# Power.net
KiCad netlist of a schematic drawn in Altium Designer
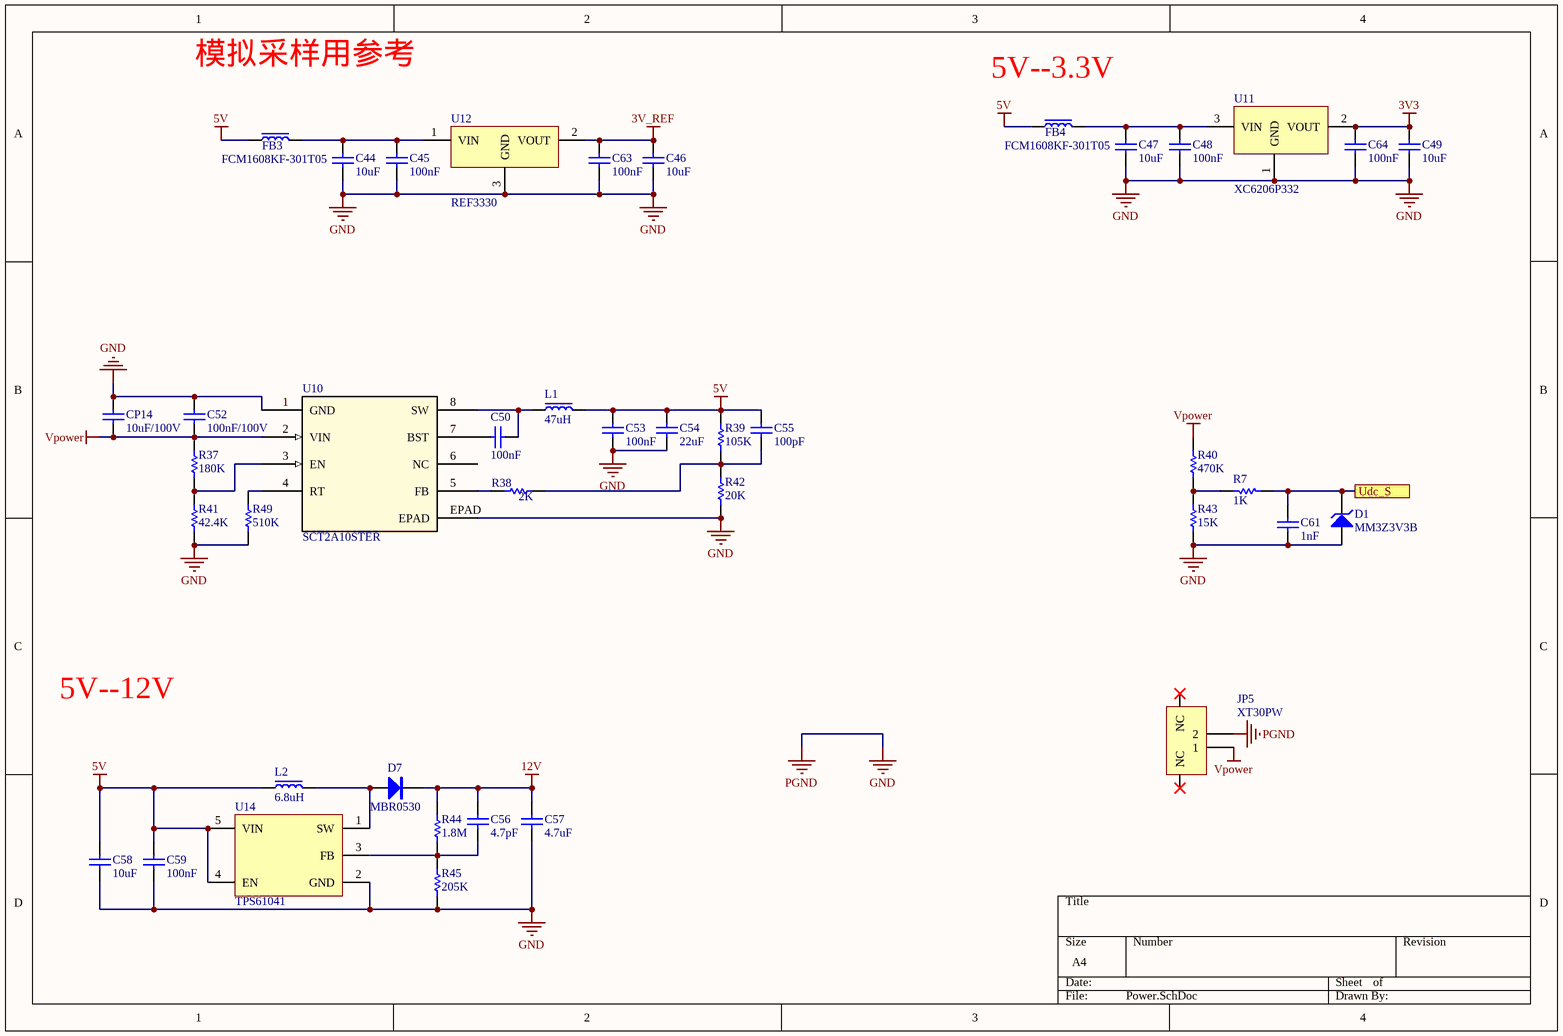
[diagram p0: Power.SchDoc]

(export (version "E")
  (design (tool "Eeschema 10.0.6"))
  (components
    (comp (ref "C44") (value "10uF") (footprint "C0603") (libsource (lib "Cap") (part "Cap")))
    (comp (ref "C45") (value "100nF") (footprint "C0603") (libsource (lib "Cap") (part "Cap")))
    (comp (ref "C46") (value "10uF") (footprint "C0603") (libsource (lib "Cap") (part "Cap")))
    (comp (ref "C47") (value "10uF") (footprint "C0603") (libsource (lib "Cap") (part "Cap")))
    (comp (ref "C48") (value "100nF") (footprint "C0603") (libsource (lib "Cap") (part "Cap")))
    (comp (ref "C49") (value "10uF") (footprint "C0603") (libsource (lib "Cap") (part "Cap")))
    (comp (ref "C50") (value "100nF") (footprint "C0603") (libsource (lib "Cap") (part "Cap")))
    (comp (ref "C52") (value "100nF/100V") (footprint "C0603") (libsource (lib "Cap") (part "Cap")))
    (comp (ref "C53") (value "100nF") (footprint "C0603") (libsource (lib "Cap") (part "Cap")))
    (comp (ref "C54") (value "22uF") (footprint "C0805") (libsource (lib "Cap") (part "Cap")))
    (comp (ref "C55") (value "100pF") (footprint "C0603") (libsource (lib "Cap") (part "Cap")))
    (comp (ref "C56") (value "4.7pF") (footprint "C0603") (libsource (lib "Cap") (part "Cap")))
    (comp (ref "C57") (value "4.7uF") (footprint "C0805") (libsource (lib "Cap") (part "Cap")))
    (comp (ref "C58") (value "10uF") (footprint "C0805") (libsource (lib "Cap") (part "Cap")))
    (comp (ref "C59") (value "100nF") (footprint "C0603") (libsource (lib "Cap") (part "Cap")))
    (comp (ref "C61") (value "1nF") (footprint "C0402") (libsource (lib "Cap") (part "Cap")))
    (comp (ref "C63") (value "100nF") (footprint "C0603") (libsource (lib "Cap") (part "Cap")))
    (comp (ref "C64") (value "100nF") (footprint "C0603") (libsource (lib "Cap") (part "Cap")))
    (comp (ref "CP14") (value "10uF/100V") (footprint "C1206") (libsource (lib "Cap") (part "Cap")))
    (comp (ref "D1")
      (value "MM3Z3V3B")
      (footprint "SOD-323")
      (description "3.14V~3.47V\r\n300mW")
      (libsource (lib "NTlib") (part "MM3Z3V3B"))
    )
    (comp (ref "D7")
      (value "MBR0530")
      (footprint "SOD-123")
      (description "30V 0.5A")
      (libsource (lib "All lib") (part "MBR0530"))
    )
    (comp (ref "FB3")
      (value "FCM1608KF-301T05")
      (footprint "FB 0402")
      (description "磁珠")
      (libsource (lib "All lib") (part "FB"))
    )
    (comp (ref "FB4")
      (value "FCM1608KF-301T05")
      (footprint "FB 0402")
      (description "磁珠")
      (libsource (lib "All lib") (part "FB"))
    )
    (comp (ref "JP5") (value "XT30PW") (footprint "XT30PW-M") (libsource (lib "All lib") (part "XT30PW")))
    (comp (ref "L1")
      (value "47uH")
      (footprint "L 0630")
      (description "功率屏蔽电感")
      (libsource (lib "All lib") (part "L-CDRH"))
    )
    (comp (ref "L2")
      (value "6.8uH")
      (footprint "L 0530")
      (description "功率屏蔽电感")
      (libsource (lib "All lib") (part "L-CDRH"))
    )
    (comp (ref "R7") (value "1K") (footprint "R0402") (libsource (lib "Res") (part "RES")))
    (comp (ref "R37") (value "180K") (footprint "R0603") (libsource (lib "Res") (part "RES")))
    (comp (ref "R38") (value "2K") (footprint "R0603") (libsource (lib "Res") (part "RES")))
    (comp (ref "R39") (value "105K") (footprint "R0603") (libsource (lib "Res") (part "RES")))
    (comp (ref "R40") (value "470K") (footprint "R0402") (libsource (lib "Res") (part "RES")))
    (comp (ref "R41") (value "42.4K") (footprint "R0603") (libsource (lib "Res") (part "RES")))
    (comp (ref "R42") (value "20K") (footprint "R0603") (libsource (lib "Res") (part "RES")))
    (comp (ref "R43") (value "15K") (footprint "R0402") (libsource (lib "Res") (part "RES")))
    (comp (ref "R44") (value "1.8M") (footprint "R0603") (libsource (lib "Res") (part "RES")))
    (comp (ref "R45") (value "205K") (footprint "R0603") (libsource (lib "Res") (part "RES")))
    (comp (ref "R49") (value "510K") (footprint "R0603") (libsource (lib "Res") (part "RES")))
    (comp (ref "U10")
      (value "SCT2A10STER")
      (footprint "DDA8_3P1X2P41-L")
      (description "No Description Available")
      (libsource (lib "All lib") (part "SCT2A10STER"))
    )
    (comp (ref "U11")
      (value "XC6206P332")
      (footprint "SOT23-3L")
      (description "VIN < 6V")
      (libsource (lib "All lib") (part "XC6206"))
    )
    (comp (ref "U12")
      (value "REF3330")
      (footprint "SOT23-3L")
      (description "TI 电压基准")
      (libsource (lib "All lib") (part "REF33XX"))
    )
    (comp (ref "U14")
      (value "TPS61041")
      (footprint "SOT23-5L")
      (description "Boost DC-DC")
      (libsource (lib "All lib") (part "TPS6104x"))
    )
  )
  (nets
    (net (code "1") (name "/Udc_S") (class "Default")
      (node (ref "C61") (pin "1") (pinfunction "1_1") (pintype "passive"))
      (node (ref "D1") (pin "K") (pinfunction "K_K") (pintype "passive"))
      (node (ref "R7") (pin "2") (pinfunction "2_2") (pintype "passive"))
    )
    (net (code "2") (name "3V3") (class "Default")
      (node (ref "C49") (pin "2") (pinfunction "2_2") (pintype "passive"))
      (node (ref "C64") (pin "2") (pinfunction "2_2") (pintype "passive"))
      (node (ref "U11") (pin "2") (pinfunction "VOUT_2") (pintype "passive"))
    )
    (net (code "3") (name "3V_REF") (class "Default")
      (node (ref "C46") (pin "2") (pinfunction "2_2") (pintype "passive"))
      (node (ref "C63") (pin "2") (pinfunction "2_2") (pintype "passive"))
      (node (ref "U12") (pin "2") (pinfunction "VOUT_2") (pintype "passive"))
    )
    (net (code "4") (name "5V") (class "Default")
      (node (ref "C53") (pin "2") (pinfunction "2_2") (pintype "passive"))
      (node (ref "C54") (pin "1") (pinfunction "1_1") (pintype "passive"))
      (node (ref "C55") (pin "1") (pinfunction "1_1") (pintype "passive"))
      (node (ref "C58") (pin "2") (pinfunction "2_2") (pintype "passive"))
      (node (ref "C59") (pin "2") (pinfunction "2_2") (pintype "passive"))
      (node (ref "FB3") (pin "1") (pinfunction "1_1") (pintype "passive"))
      (node (ref "FB4") (pin "1") (pinfunction "1_1") (pintype "passive"))
      (node (ref "L1") (pin "2") (pinfunction "2_2") (pintype "passive"))
      (node (ref "L2") (pin "1") (pinfunction "1_1") (pintype "passive"))
      (node (ref "R39") (pin "2") (pinfunction "2_2") (pintype "passive"))
      (node (ref "U14") (pin "4") (pinfunction "EN_4") (pintype "passive"))
      (node (ref "U14") (pin "5") (pinfunction "VIN_5") (pintype "passive"))
    )
    (net (code "5") (name "12V") (class "Default")
      (node (ref "C56") (pin "2") (pinfunction "2_2") (pintype "passive"))
      (node (ref "C57") (pin "2") (pinfunction "2_2") (pintype "passive"))
      (node (ref "D7") (pin "K") (pinfunction "K_K") (pintype "passive"))
      (node (ref "R44") (pin "1") (pinfunction "1_1") (pintype "passive"))
    )
    (net (code "6") (name "GND") (class "Default")
      (node (ref "C44") (pin "1") (pinfunction "1_1") (pintype "passive"))
      (node (ref "C45") (pin "1") (pinfunction "1_1") (pintype "passive"))
      (node (ref "C46") (pin "1") (pinfunction "1_1") (pintype "passive"))
      (node (ref "C47") (pin "1") (pinfunction "1_1") (pintype "passive"))
      (node (ref "C48") (pin "1") (pinfunction "1_1") (pintype "passive"))
      (node (ref "C49") (pin "1") (pinfunction "1_1") (pintype "passive"))
      (node (ref "C52") (pin "1") (pinfunction "1_1") (pintype "passive"))
      (node (ref "C53") (pin "1") (pinfunction "1_1") (pintype "passive"))
      (node (ref "C54") (pin "2") (pinfunction "2_2") (pintype "passive"))
      (node (ref "C57") (pin "1") (pinfunction "1_1") (pintype "passive"))
      (node (ref "C58") (pin "1") (pinfunction "1_1") (pintype "passive"))
      (node (ref "C59") (pin "1") (pinfunction "1_1") (pintype "passive"))
      (node (ref "C61") (pin "2") (pinfunction "2_2") (pintype "passive"))
      (node (ref "C63") (pin "1") (pinfunction "1_1") (pintype "passive"))
      (node (ref "C64") (pin "1") (pinfunction "1_1") (pintype "passive"))
      (node (ref "CP14") (pin "1") (pinfunction "1_1") (pintype "passive"))
      (node (ref "D1") (pin "A") (pinfunction "A_A") (pintype "passive"))
      (node (ref "JP5") (pin "2") (pinfunction "2_2") (pintype "passive"))
      (node (ref "R41") (pin "1") (pinfunction "1_1") (pintype "passive"))
      (node (ref "R42") (pin "1") (pinfunction "1_1") (pintype "passive"))
      (node (ref "R43") (pin "1") (pinfunction "1_1") (pintype "passive"))
      (node (ref "R45") (pin "2") (pinfunction "2_2") (pintype "passive"))
      (node (ref "R49") (pin "1") (pinfunction "1_1") (pintype "passive"))
      (node (ref "U10") (pin "1") (pinfunction "GND_1") (pintype "power_in"))
      (node (ref "U10") (pin "EPAD") (pinfunction "EPAD_EPAD") (pintype "passive"))
      (node (ref "U11") (pin "1") (pinfunction "GND_1") (pintype "passive"))
      (node (ref "U12") (pin "3") (pinfunction "GND_3") (pintype "passive"))
      (node (ref "U14") (pin "2") (pinfunction "GND_2") (pintype "passive"))
    )
    (net (code "7") (name "Net-(C55-Pad2)") (class "Default")
      (node (ref "C55") (pin "2") (pinfunction "2_2") (pintype "passive"))
      (node (ref "R38") (pin "1") (pinfunction "1_1") (pintype "passive"))
      (node (ref "R39") (pin "1") (pinfunction "1_1") (pintype "passive"))
      (node (ref "R42") (pin "2") (pinfunction "2_2") (pintype "passive"))
    )
    (net (code "8") (name "Net-(R40-Pad1)") (class "Default")
      (node (ref "R40") (pin "1") (pinfunction "1_1") (pintype "passive"))
      (node (ref "R43") (pin "2") (pinfunction "2_2") (pintype "passive"))
      (node (ref "R7") (pin "1") (pinfunction "1_1") (pintype "passive"))
    )
    (net (code "9") (name "Net-(U10-BST)") (class "Default")
      (node (ref "C50") (pin "1") (pinfunction "1_1") (pintype "passive"))
      (node (ref "U10") (pin "7") (pinfunction "BST_7") (pintype "passive"))
    )
    (net (code "10") (name "Net-(U10-EN)") (class "Default")
      (node (ref "R37") (pin "1") (pinfunction "1_1") (pintype "passive"))
      (node (ref "R41") (pin "2") (pinfunction "2_2") (pintype "passive"))
      (node (ref "U10") (pin "3") (pinfunction "EN_3") (pintype "input"))
    )
    (net (code "11") (name "Net-(U10-FB)") (class "Default")
      (node (ref "R38") (pin "2") (pinfunction "2_2") (pintype "passive"))
      (node (ref "U10") (pin "5") (pinfunction "FB_5") (pintype "passive"))
    )
    (net (code "12") (name "Net-(U10-RT)") (class "Default")
      (node (ref "R49") (pin "2") (pinfunction "2_2") (pintype "passive"))
      (node (ref "U10") (pin "4") (pinfunction "RT_4") (pintype "passive"))
    )
    (net (code "13") (name "Net-(U10-SW)") (class "Default")
      (node (ref "C50") (pin "2") (pinfunction "2_2") (pintype "passive"))
      (node (ref "L1") (pin "1") (pinfunction "1_1") (pintype "passive"))
      (node (ref "U10") (pin "8") (pinfunction "SW_8") (pintype "passive"))
    )
    (net (code "14") (name "Net-(U11-VIN)") (class "Default")
      (node (ref "C47") (pin "2") (pinfunction "2_2") (pintype "passive"))
      (node (ref "C48") (pin "2") (pinfunction "2_2") (pintype "passive"))
      (node (ref "FB4") (pin "2") (pinfunction "2_2") (pintype "passive"))
      (node (ref "U11") (pin "3") (pinfunction "VIN_3") (pintype "passive"))
    )
    (net (code "15") (name "Net-(U12-VIN)") (class "Default")
      (node (ref "C44") (pin "2") (pinfunction "2_2") (pintype "passive"))
      (node (ref "C45") (pin "2") (pinfunction "2_2") (pintype "passive"))
      (node (ref "FB3") (pin "2") (pinfunction "2_2") (pintype "passive"))
      (node (ref "U12") (pin "1") (pinfunction "VIN_1") (pintype "passive"))
    )
    (net (code "16") (name "Net-(U14-FB)") (class "Default")
      (node (ref "C56") (pin "1") (pinfunction "1_1") (pintype "passive"))
      (node (ref "R44") (pin "2") (pinfunction "2_2") (pintype "passive"))
      (node (ref "R45") (pin "1") (pinfunction "1_1") (pintype "passive"))
      (node (ref "U14") (pin "3") (pinfunction "FB_3") (pintype "passive"))
    )
    (net (code "17") (name "Net-(U14-SW)") (class "Default")
      (node (ref "D7") (pin "A") (pinfunction "A_A") (pintype "passive"))
      (node (ref "L2") (pin "2") (pinfunction "2_2") (pintype "passive"))
      (node (ref "U14") (pin "1") (pinfunction "SW_1") (pintype "passive"))
    )
    (net (code "18") (name "Vpower") (class "Default")
      (node (ref "C52") (pin "2") (pinfunction "2_2") (pintype "passive"))
      (node (ref "CP14") (pin "2") (pinfunction "2_2") (pintype "passive"))
      (node (ref "JP5") (pin "1") (pinfunction "1_1") (pintype "passive"))
      (node (ref "R37") (pin "2") (pinfunction "2_2") (pintype "passive"))
      (node (ref "R40") (pin "2") (pinfunction "2_2") (pintype "passive"))
      (node (ref "U10") (pin "2") (pinfunction "VIN_2") (pintype "input"))
    )
    (net (code "19") (name "unconnected-(JP5-NC-Pad3)") (class "Default")
      (node (ref "JP5") (pin "3") (pinfunction "NC_3") (pintype "passive+no_connect"))
    )
    (net (code "20") (name "unconnected-(JP5-NC-Pad4)") (class "Default")
      (node (ref "JP5") (pin "4") (pinfunction "NC_4") (pintype "passive+no_connect"))
    )
    (net (code "21") (name "unconnected-(U10-NC-Pad6)") (class "Default")
      (node (ref "U10") (pin "6") (pinfunction "NC_6") (pintype "power_in"))
    )
  )
)
